# LoraFtdi.net
KiCad netlist of a schematic drawn in Altium Designer
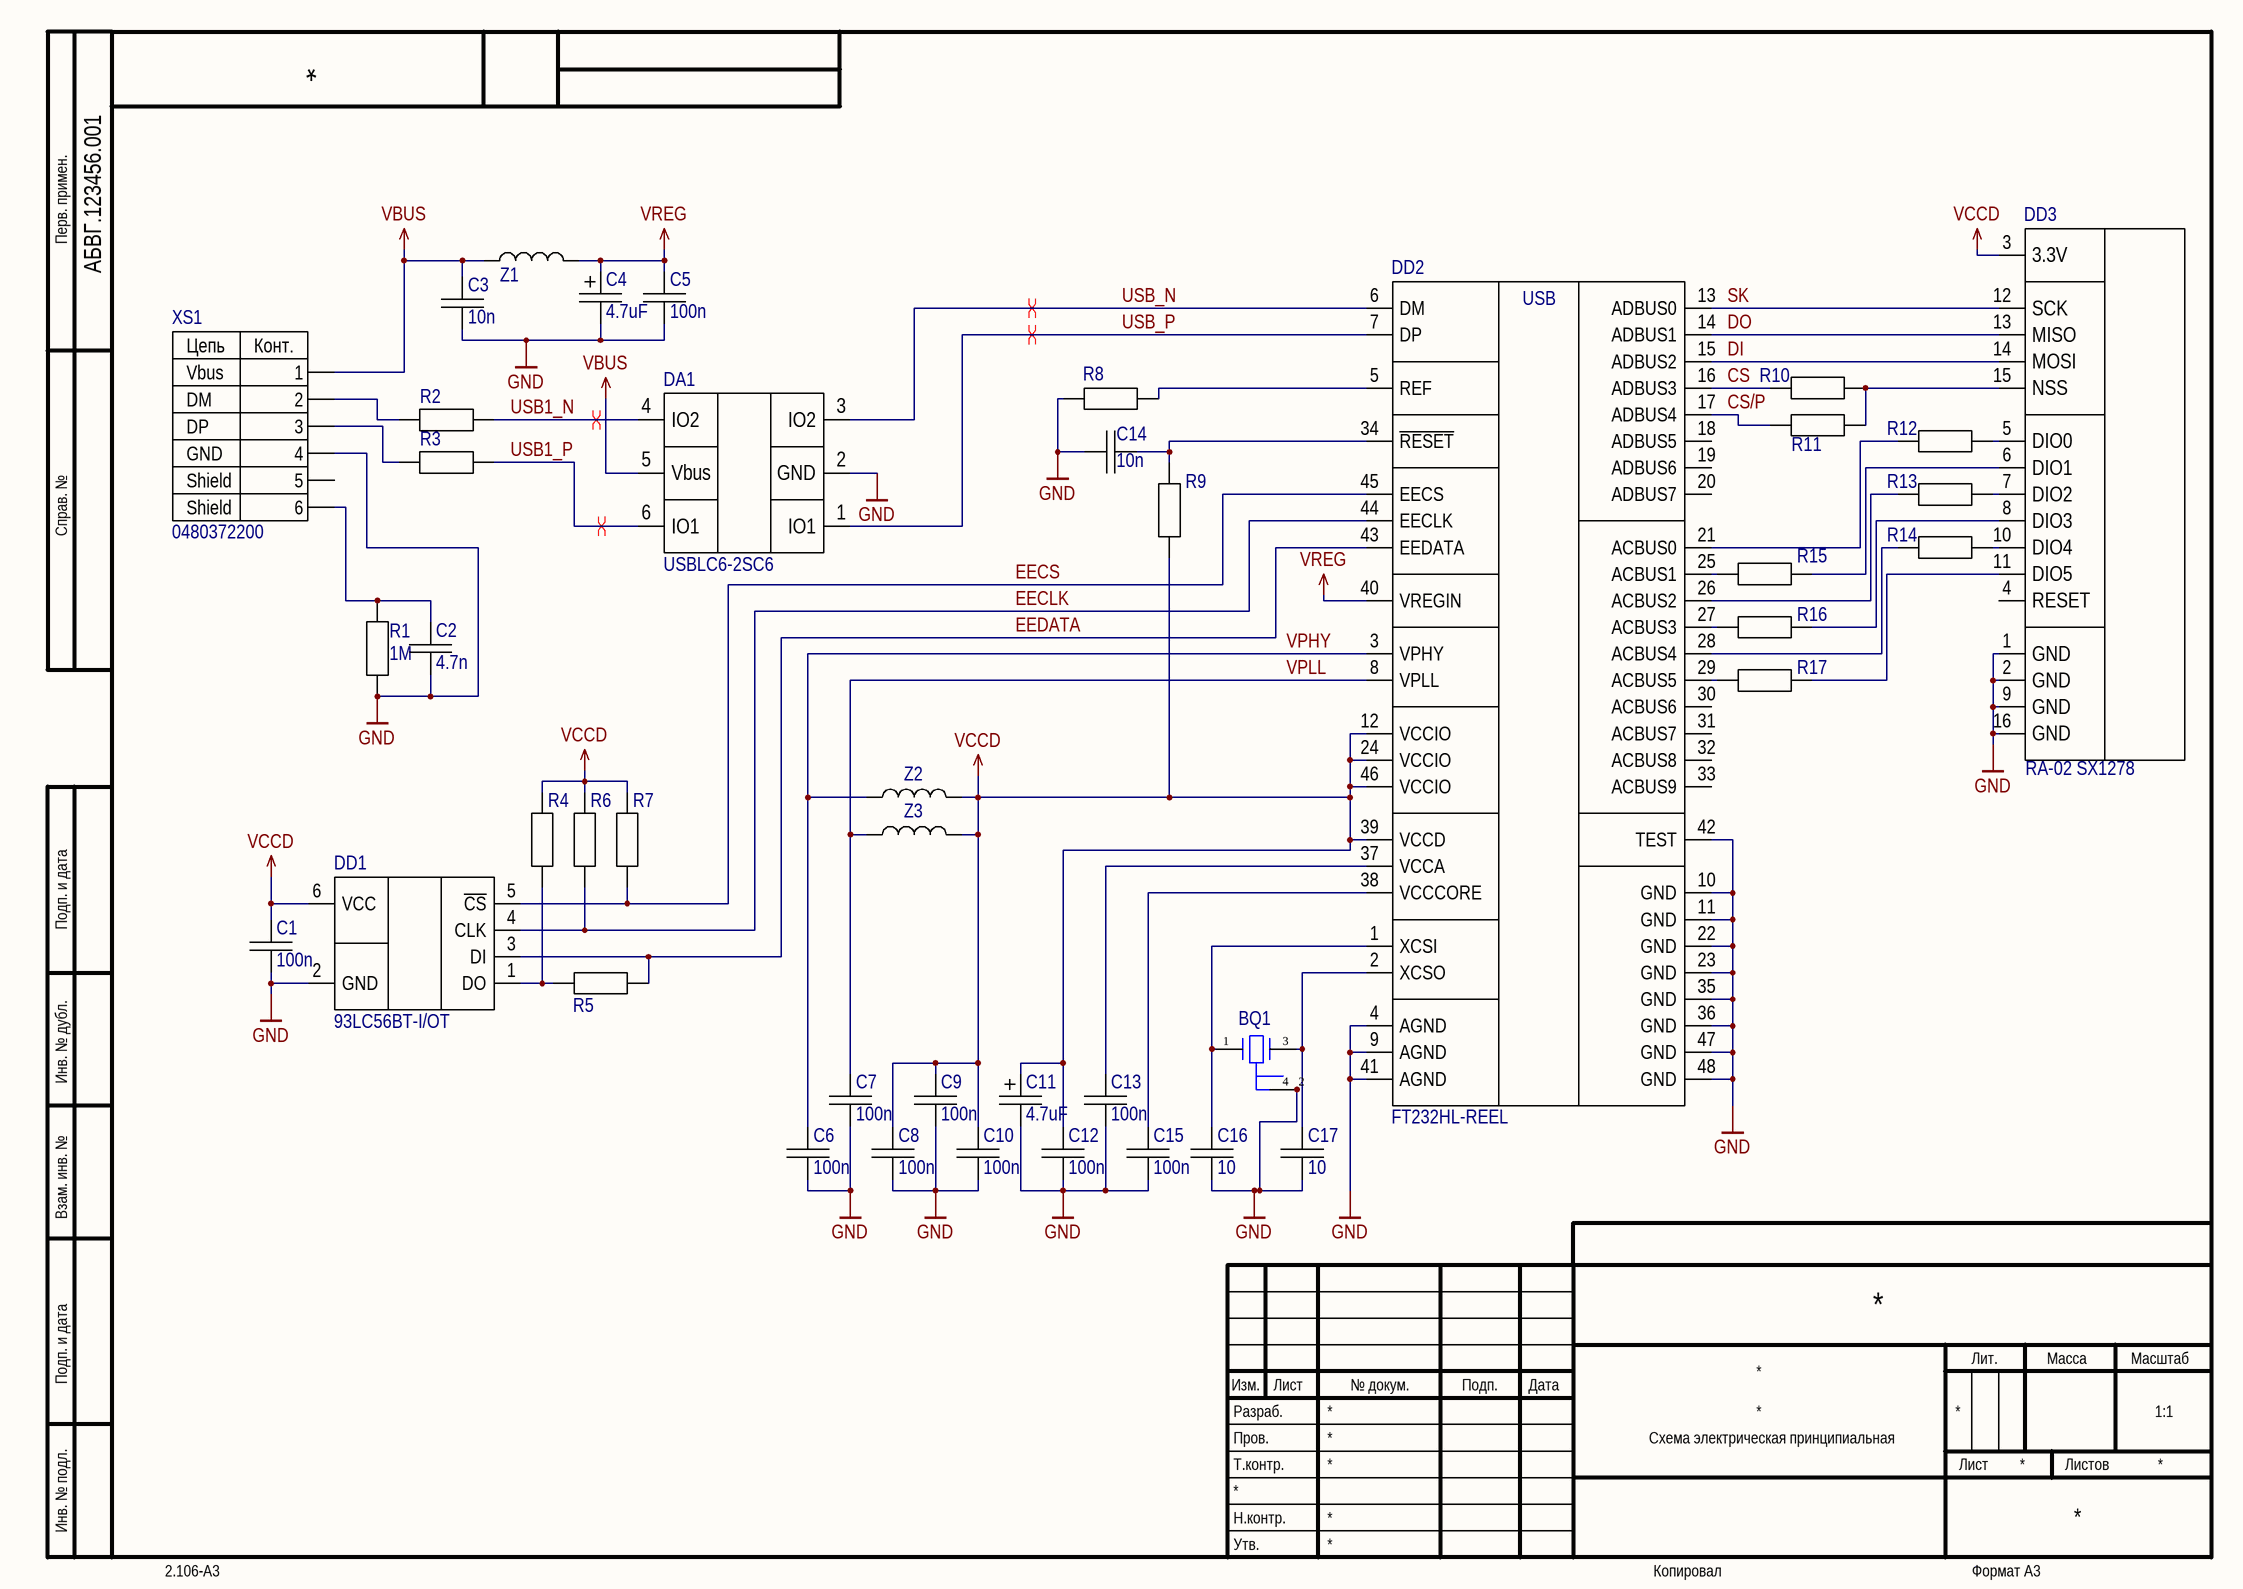
[diagram p0: LoraFtdi.SchDoc]

(export (version "E")
  (design (tool "Eeschema 10.0.6"))
  (components
    (comp (ref "BQ1")
      (value "ABM8G-12.000MHZ-4Y-T3")
      (footprint "Abracon_ABM8G_0")
      (libsource (lib "Crys_Abracon_ABM8G-12.000MHZ-4Y-T3_eec") (part "ABM8G-12.000MHZ-4Y-T3"))
    )
    (comp (ref "C1")
      (value "100n")
      (footprint "1608[0603]")
      (description "Конденсатор 1.6x0.8 мм")
      (fields (field (name "TOLERANCE") "±10%"))
      (libsource (lib "RPSLib") (part "CC1608"))
    )
    (comp (ref "C2")
      (value "4.7n")
      (footprint "1608[0603]")
      (description "Конденсатор 1.6x0.8 мм")
      (fields (field (name "TOLERANCE") "±10%"))
      (libsource (lib "RPSLib") (part "CC1608"))
    )
    (comp (ref "C3")
      (value "10n")
      (footprint "CAPC1608X09L")
      (description "Конденсатор 1.6x0.8 мм")
      (fields (field (name "TOLERANCE") "±10%"))
      (libsource (lib "RPSLib") (part "CC1608"))
    )
    (comp (ref "C4")
      (value "4.7uF")
      (footprint "CAPMP3216X16N-A")
      (description "Tantalum Surface Mount Capacitor, Size A")
      (fields (field (name "VOLTAGE") "16"))
      (libsource (lib "RPSLib") (part "CT3216-A"))
    )
    (comp (ref "C5")
      (value "100n")
      (footprint "CAPC1608X09L")
      (description "Конденсатор 1.6x0.8 мм")
      (fields (field (name "TOLERANCE") "±10%"))
      (libsource (lib "RPSLib") (part "CC1608"))
    )
    (comp (ref "C6")
      (value "100n")
      (footprint "CAPC1608X09L")
      (description "Конденсатор 1.6x0.8 мм")
      (fields (field (name "TOLERANCE") "±10%"))
      (libsource (lib "RPSLib") (part "CC1608"))
    )
    (comp (ref "C7")
      (value "100n")
      (footprint "CAPC1608X09L")
      (description "Конденсатор 1.6x0.8 мм")
      (fields (field (name "TOLERANCE") "±10%"))
      (libsource (lib "RPSLib") (part "CC1608"))
    )
    (comp (ref "C8")
      (value "100n")
      (footprint "CAPC1608X09L")
      (description "Конденсатор 1.6x0.8 мм")
      (fields (field (name "TOLERANCE") "±10%"))
      (libsource (lib "RPSLib") (part "CC1608"))
    )
    (comp (ref "C9")
      (value "100n")
      (footprint "CAPC1608X09L")
      (description "Конденсатор 1.6x0.8 мм")
      (fields (field (name "TOLERANCE") "±10%"))
      (libsource (lib "RPSLib") (part "CC1608"))
    )
    (comp (ref "C10")
      (value "100n")
      (footprint "CAPC1608X09L")
      (description "Конденсатор 1.6x0.8 мм")
      (fields (field (name "TOLERANCE") "±10%"))
      (libsource (lib "RPSLib") (part "CC1608"))
    )
    (comp (ref "C11")
      (value "4.7uF")
      (footprint "CAPMP3216X16N-A")
      (description "Tantalum Surface Mount Capacitor, Size A")
      (fields (field (name "VOLTAGE") "16"))
      (libsource (lib "RPSLib") (part "CT3216-A"))
    )
    (comp (ref "C12")
      (value "100n")
      (footprint "CAPC1608X09L")
      (description "Конденсатор 1.6x0.8 мм")
      (fields (field (name "TOLERANCE") "±10%"))
      (libsource (lib "RPSLib") (part "CC1608"))
    )
    (comp (ref "C13")
      (value "100n")
      (footprint "CAPC1608X09L")
      (description "Конденсатор 1.6x0.8 мм")
      (fields (field (name "TOLERANCE") "±10%"))
      (libsource (lib "RPSLib") (part "CC1608"))
    )
    (comp (ref "C14")
      (value "10n")
      (footprint "CAPC1608X09L")
      (description "Конденсатор 1.6x0.8 мм")
      (fields (field (name "TOLERANCE") "±10%"))
      (libsource (lib "RPSLib") (part "CC1608"))
    )
    (comp (ref "C15")
      (value "100n")
      (footprint "CAPC1608X09L")
      (description "Конденсатор 1.6x0.8 мм")
      (fields (field (name "TOLERANCE") "±10%"))
      (libsource (lib "RPSLib") (part "CC1608"))
    )
    (comp (ref "C16")
      (value "10")
      (footprint "CAPC1608X09L")
      (description "Конденсатор 1.6x0.8 мм")
      (fields (field (name "TOLERANCE") "±10%"))
      (libsource (lib "RPSLib") (part "CC1608"))
    )
    (comp (ref "C17")
      (value "10")
      (footprint "1608[0603]")
      (description "Конденсатор 1.6x0.8 мм")
      (fields (field (name "TOLERANCE") "±10%"))
      (libsource (lib "RPSLib") (part "CC1608"))
    )
    (comp (ref "DA1")
      (value "USBLC6-2SC6")
      (footprint "SOT95P280X145-6N")
      (description "USB protection IC")
      (fields (field (name "MANUFACTURER") "STMicroelectronics"))
      (libsource (lib "RPSLib") (part "USBLC6-2SC6"))
    )
    (comp (ref "DD1")
      (value "93LC56BT-I/OT")
      (footprint "SOT95P280X145-6N")
      (description "IC EEPROM 2K SPI 2MHZ SOT23-6")
      (fields (field (name "MANUFACTURER") "Microchip"))
      (libsource (lib "RPSLib") (part "93LC56BT-I/OT"))
    )
    (comp (ref "DD2")
      (value "FT232HL-REEL")
      (footprint "TSQFP50P900X900X160-48N")
      (description "IC HS USB TO UART/FIFO 48LQFP")
      (fields (field (name "MANUFACTURER") "FTDI"))
      (libsource (lib "RPSLib") (part "FT232HL-REEL"))
    )
    (comp (ref "DD3") (value "RA-02 SX1278") (footprint "RA-02") (libsource (lib "RA-02") (part "RA-02")))
    (comp (ref "R1")
      (value "1M")
      (footprint "J1-0603")
      (description "Резистор 1.6x0.8 мм")
      (fields (field (name "TOLERANCE") "±5%") (field (name "MANUFACTURER PART NUMBER") "RC0603JR-071ML"))
      (libsource (lib "RPSLib") (part "R1608"))
    )
    (comp (ref "R2")
      (value "R1608")
      (footprint "RESC1608X05N")
      (description "Резистор 1.6x0.8 мм")
      (fields (field (name "TOLERANCE") "±1%"))
      (libsource (lib "RPSLib") (part "R1608"))
    )
    (comp (ref "R3")
      (value "R1608")
      (footprint "RESC1608X05N")
      (description "Резистор 1.6x0.8 мм")
      (fields (field (name "TOLERANCE") "±1%"))
      (libsource (lib "RPSLib") (part "R1608"))
    )
    (comp (ref "R4")
      (value "R1608")
      (footprint "RESC1608X05N")
      (description "Резистор 1.6x0.8 мм")
      (fields (field (name "TOLERANCE") "±5%"))
      (libsource (lib "RPSLib") (part "R1608"))
    )
    (comp (ref "R5")
      (value "R1608")
      (footprint "RESC1608X05N")
      (description "Резистор 1.6x0.8 мм")
      (fields (field (name "TOLERANCE") "±5%"))
      (libsource (lib "RPSLib") (part "R1608"))
    )
    (comp (ref "R6")
      (value "R1608")
      (footprint "RESC1608X05N")
      (description "Резистор 1.6x0.8 мм")
      (fields (field (name "TOLERANCE") "±5%"))
      (libsource (lib "RPSLib") (part "R1608"))
    )
    (comp (ref "R7")
      (value "R1608")
      (footprint "RESC1608X05N")
      (description "Резистор 1.6x0.8 мм")
      (fields (field (name "TOLERANCE") "±5%"))
      (libsource (lib "RPSLib") (part "R1608"))
    )
    (comp (ref "R8")
      (value "R1608")
      (footprint "RESC1608X05N")
      (description "Резистор 1.6x0.8 мм")
      (fields (field (name "TOLERANCE") "±5%"))
      (libsource (lib "RPSLib") (part "R1608"))
    )
    (comp (ref "R9")
      (value "R1608")
      (footprint "RESC1608X05N")
      (description "Резистор 1.6x0.8 мм")
      (fields (field (name "TOLERANCE") "±5%"))
      (libsource (lib "RPSLib") (part "R1608"))
    )
    (comp (ref "R10")
      (value "R0603")
      (footprint "RESC0603X02N")
      (description "Резистор 0.6x0.3 мм")
      (libsource (lib "RPSLib") (part "R0603"))
    )
    (comp (ref "R11")
      (value "R0603")
      (footprint "RESC0603X02N")
      (description "Резистор 0.6x0.3 мм")
      (libsource (lib "RPSLib") (part "R0603"))
    )
    (comp (ref "R12")
      (value "R0603")
      (footprint "RESC0603X02N")
      (description "Резистор 0.6x0.3 мм")
      (libsource (lib "RPSLib") (part "R0603"))
    )
    (comp (ref "R13")
      (value "R0603")
      (footprint "RESC0603X02N")
      (description "Резистор 0.6x0.3 мм")
      (libsource (lib "RPSLib") (part "R0603"))
    )
    (comp (ref "R14")
      (value "R0603")
      (footprint "RESC0603X02N")
      (description "Резистор 0.6x0.3 мм")
      (libsource (lib "RPSLib") (part "R0603"))
    )
    (comp (ref "R15")
      (value "R0603")
      (footprint "RESC0603X02N")
      (description "Резистор 0.6x0.3 мм")
      (libsource (lib "RPSLib") (part "R0603"))
    )
    (comp (ref "R16")
      (value "R0603")
      (footprint "RESC0603X02N")
      (description "Резистор 0.6x0.3 мм")
      (libsource (lib "RPSLib") (part "R0603"))
    )
    (comp (ref "R17")
      (value "R0603")
      (footprint "RESC0603X02N")
      (description "Резистор 0.6x0.3 мм")
      (libsource (lib "RPSLib") (part "R0603"))
    )
    (comp (ref "XS1")
      (value "Conn_Molex_0480372200_eec")
      (footprint "Molex_0480372200_0")
      (description "CONN PLUG USB A 4POS SMD R/A")
      (fields
        (field (name "MANUFACTURER") "Molex")
        (field (name "MOUSER PART NUMBER") "538-48037-2200")
        (field (name "PART NUMBER") "0480372200")
      )
      (libsource (lib "Conn_Molex_0480372200_eec") (part "Conn_Molex_0480372200_eec"))
    )
    (comp (ref "Z1")
      (value "BLM18AG601SN1D")
      (footprint "INDC1608X08N_BLM18AG")
      (description "FERRITE CHIP 600 OHM 500MA 0603")
      (fields (field (name "MANUFACTURER") "Murata") (field (name "TOLERANCE") "25%"))
      (libsource (lib "RPSLib") (part "BLM18AG601SN1D"))
    )
    (comp (ref "Z2")
      (value "BLM18AG601SN1D")
      (footprint "INDC1608L")
      (description "FERRITE CHIP 600 OHM 500MA 0603")
      (fields (field (name "MANUFACTURER") "Murata") (field (name "TOLERANCE") "25%"))
      (libsource (lib "RPSLib") (part "BLM18AG601SN1D"))
    )
    (comp (ref "Z3")
      (value "BLM18AG601SN1D")
      (footprint "INDC1608L")
      (description "FERRITE CHIP 600 OHM 500MA 0603")
      (fields (field (name "MANUFACTURER") "Murata") (field (name "TOLERANCE") "25%"))
      (libsource (lib "RPSLib") (part "BLM18AG601SN1D"))
    )
  )
  (nets
    (net (code "1") (name "/CS") (class "Default")
      (node (ref "DD2") (pin "16") (pinfunction "ADBUS3_16") (pintype "passive"))
      (node (ref "R10") (pin "1") (pinfunction "1_1") (pintype "passive"))
    )
    (net (code "2") (name "/CS{slash}P") (class "Default")
      (node (ref "DD2") (pin "17") (pinfunction "ADBUS4_17") (pintype "passive"))
      (node (ref "R11") (pin "1") (pinfunction "1_1") (pintype "passive"))
    )
    (net (code "3") (name "/DI") (class "Default")
      (node (ref "DD2") (pin "15") (pinfunction "ADBUS2_15") (pintype "passive"))
      (node (ref "DD3") (pin "14") (pinfunction "MOSI_14") (pintype "passive"))
    )
    (net (code "4") (name "/DO") (class "Default")
      (node (ref "DD2") (pin "14") (pinfunction "ADBUS1_14") (pintype "passive"))
      (node (ref "DD3") (pin "13") (pinfunction "MISO_13") (pintype "passive"))
    )
    (net (code "5") (name "/EECLK") (class "Default")
      (node (ref "DD1") (pin "4") (pinfunction "CLK_4") (pintype "passive"))
      (node (ref "DD2") (pin "44") (pinfunction "EECLK_44") (pintype "passive"))
      (node (ref "R6") (pin "1") (pinfunction "1_1") (pintype "passive"))
    )
    (net (code "6") (name "/EECS") (class "Default")
      (node (ref "DD1") (pin "5") (pinfunction "~{CS}_5") (pintype "passive"))
      (node (ref "DD2") (pin "45") (pinfunction "EECS_45") (pintype "passive"))
      (node (ref "R7") (pin "1") (pinfunction "1_1") (pintype "passive"))
    )
    (net (code "7") (name "/EEDATA") (class "Default")
      (node (ref "DD1") (pin "3") (pinfunction "DI_3") (pintype "passive"))
      (node (ref "DD2") (pin "43") (pinfunction "EEDATA_43") (pintype "passive"))
      (node (ref "R5") (pin "1") (pinfunction "1_1") (pintype "passive"))
    )
    (net (code "8") (name "/SK") (class "Default")
      (node (ref "DD2") (pin "13") (pinfunction "ADBUS0_13") (pintype "passive"))
      (node (ref "DD3") (pin "12") (pinfunction "SCK_12") (pintype "passive"))
    )
    (net (code "9") (name "/USB1_N") (class "Default")
      (node (ref "DA1") (pin "4") (pinfunction "IO2_4") (pintype "passive"))
      (node (ref "R2") (pin "1") (pinfunction "1_1") (pintype "passive"))
    )
    (net (code "10") (name "/USB1_P") (class "Default")
      (node (ref "DA1") (pin "6") (pinfunction "IO1_6") (pintype "passive"))
      (node (ref "R3") (pin "1") (pinfunction "1_1") (pintype "passive"))
    )
    (net (code "11") (name "/USB_N") (class "Default")
      (node (ref "DA1") (pin "3") (pinfunction "IO2_3") (pintype "passive"))
      (node (ref "DD2") (pin "6") (pinfunction "DM_6") (pintype "passive"))
    )
    (net (code "12") (name "/USB_P") (class "Default")
      (node (ref "DA1") (pin "1") (pinfunction "IO1_1") (pintype "passive"))
      (node (ref "DD2") (pin "7") (pinfunction "DP_7") (pintype "passive"))
    )
    (net (code "13") (name "/VPHY") (class "Default")
      (node (ref "C6") (pin "2") (pinfunction "2_2") (pintype "passive"))
      (node (ref "DD2") (pin "3") (pinfunction "VPHY_3") (pintype "passive"))
      (node (ref "Z2") (pin "1") (pinfunction "1_1") (pintype "passive"))
    )
    (net (code "14") (name "/VPLL") (class "Default")
      (node (ref "C7") (pin "2") (pinfunction "2_2") (pintype "passive"))
      (node (ref "DD2") (pin "8") (pinfunction "VPLL_8") (pintype "passive"))
      (node (ref "Z3") (pin "1") (pinfunction "1_1") (pintype "passive"))
    )
    (net (code "15") (name "GND") (class "Default")
      (node (ref "BQ1") (pin "2") (pinfunction "GND_2") (pintype "passive"))
      (node (ref "BQ1") (pin "4") (pinfunction "GND_4") (pintype "passive"))
      (node (ref "C1") (pin "1") (pinfunction "1_1") (pintype "passive"))
      (node (ref "C10") (pin "1") (pinfunction "1_1") (pintype "passive"))
      (node (ref "C11") (pin "2") (pinfunction "2_2") (pintype "passive"))
      (node (ref "C12") (pin "1") (pinfunction "1_1") (pintype "passive"))
      (node (ref "C13") (pin "1") (pinfunction "1_1") (pintype "passive"))
      (node (ref "C14") (pin "2") (pinfunction "2_2") (pintype "passive"))
      (node (ref "C15") (pin "1") (pinfunction "1_1") (pintype "passive"))
      (node (ref "C16") (pin "1") (pinfunction "1_1") (pintype "passive"))
      (node (ref "C17") (pin "1") (pinfunction "1_1") (pintype "passive"))
      (node (ref "C2") (pin "1") (pinfunction "1_1") (pintype "passive"))
      (node (ref "C3") (pin "1") (pinfunction "1_1") (pintype "passive"))
      (node (ref "C4") (pin "2") (pinfunction "2_2") (pintype "passive"))
      (node (ref "C5") (pin "1") (pinfunction "1_1") (pintype "passive"))
      (node (ref "C6") (pin "1") (pinfunction "1_1") (pintype "passive"))
      (node (ref "C7") (pin "1") (pinfunction "1_1") (pintype "passive"))
      (node (ref "C8") (pin "1") (pinfunction "1_1") (pintype "passive"))
      (node (ref "C9") (pin "1") (pinfunction "1_1") (pintype "passive"))
      (node (ref "DA1") (pin "2") (pinfunction "GND_2") (pintype "passive"))
      (node (ref "DD1") (pin "2") (pinfunction "GND_2") (pintype "passive"))
      (node (ref "DD2") (pin "10") (pinfunction "GND_10") (pintype "passive"))
      (node (ref "DD2") (pin "11") (pinfunction "GND_11") (pintype "passive"))
      (node (ref "DD2") (pin "22") (pinfunction "GND_22") (pintype "passive"))
      (node (ref "DD2") (pin "23") (pinfunction "GND_23") (pintype "passive"))
      (node (ref "DD2") (pin "35") (pinfunction "GND_35") (pintype "passive"))
      (node (ref "DD2") (pin "36") (pinfunction "GND_36") (pintype "passive"))
      (node (ref "DD2") (pin "4") (pinfunction "AGND_4") (pintype "passive"))
      (node (ref "DD2") (pin "41") (pinfunction "AGND_41") (pintype "passive"))
      (node (ref "DD2") (pin "42") (pinfunction "TEST_42") (pintype "passive"))
      (node (ref "DD2") (pin "47") (pinfunction "GND_47") (pintype "passive"))
      (node (ref "DD2") (pin "48") (pinfunction "GND_48") (pintype "passive"))
      (node (ref "DD2") (pin "9") (pinfunction "AGND_9") (pintype "passive"))
      (node (ref "DD3") (pin "1") (pinfunction "GND_1") (pintype "passive"))
      (node (ref "DD3") (pin "16") (pinfunction "GND_16") (pintype "passive"))
      (node (ref "DD3") (pin "2") (pinfunction "GND_2") (pintype "passive"))
      (node (ref "DD3") (pin "9") (pinfunction "GND_9") (pintype "passive"))
      (node (ref "R1") (pin "2") (pinfunction "2_2") (pintype "passive"))
      (node (ref "R8") (pin "2") (pinfunction "2_2") (pintype "passive"))
      (node (ref "XS1") (pin "4") (pinfunction "4_4") (pintype "passive"))
    )
    (net (code "16") (name "Net-(DD1-DO)") (class "Default")
      (node (ref "DD1") (pin "1") (pinfunction "DO_1") (pintype "passive"))
      (node (ref "R4") (pin "1") (pinfunction "1_1") (pintype "passive"))
      (node (ref "R5") (pin "2") (pinfunction "2_2") (pintype "passive"))
    )
    (net (code "17") (name "Net-(DD2-ACBUS0)") (class "Default")
      (node (ref "DD2") (pin "21") (pinfunction "ACBUS0_21") (pintype "passive"))
      (node (ref "R12") (pin "1") (pinfunction "1_1") (pintype "passive"))
    )
    (net (code "18") (name "Net-(DD2-ACBUS1)") (class "Default")
      (node (ref "DD2") (pin "25") (pinfunction "ACBUS1_25") (pintype "passive"))
      (node (ref "R15") (pin "1") (pinfunction "1_1") (pintype "passive"))
    )
    (net (code "19") (name "Net-(DD2-ACBUS2)") (class "Default")
      (node (ref "DD2") (pin "26") (pinfunction "ACBUS2_26") (pintype "passive"))
      (node (ref "R13") (pin "1") (pinfunction "1_1") (pintype "passive"))
    )
    (net (code "20") (name "Net-(DD2-ACBUS3)") (class "Default")
      (node (ref "DD2") (pin "27") (pinfunction "ACBUS3_27") (pintype "passive"))
      (node (ref "R16") (pin "1") (pinfunction "1_1") (pintype "passive"))
    )
    (net (code "21") (name "Net-(DD2-ACBUS4)") (class "Default")
      (node (ref "DD2") (pin "28") (pinfunction "ACBUS4_28") (pintype "passive"))
      (node (ref "R14") (pin "1") (pinfunction "1_1") (pintype "passive"))
    )
    (net (code "22") (name "Net-(DD2-ACBUS5)") (class "Default")
      (node (ref "DD2") (pin "29") (pinfunction "ACBUS5_29") (pintype "passive"))
      (node (ref "R17") (pin "1") (pinfunction "1_1") (pintype "passive"))
    )
    (net (code "23") (name "Net-(DD2-REF)") (class "Default")
      (node (ref "DD2") (pin "5") (pinfunction "REF_5") (pintype "passive"))
      (node (ref "R8") (pin "1") (pinfunction "1_1") (pintype "passive"))
    )
    (net (code "24") (name "Net-(DD2-VCCA)") (class "Default")
      (node (ref "C13") (pin "2") (pinfunction "2_2") (pintype "passive"))
      (node (ref "DD2") (pin "37") (pinfunction "VCCA_37") (pintype "passive"))
    )
    (net (code "25") (name "Net-(DD2-VCCCORE)") (class "Default")
      (node (ref "C15") (pin "2") (pinfunction "2_2") (pintype "passive"))
      (node (ref "DD2") (pin "38") (pinfunction "VCCCORE_38") (pintype "passive"))
    )
    (net (code "26") (name "Net-(DD2-XCSI)") (class "Default")
      (node (ref "BQ1") (pin "1") (pinfunction "1_1") (pintype "passive"))
      (node (ref "C16") (pin "2") (pinfunction "2_2") (pintype "passive"))
      (node (ref "DD2") (pin "1") (pinfunction "XCSI_1") (pintype "passive"))
    )
    (net (code "27") (name "Net-(DD2-XCSO)") (class "Default")
      (node (ref "BQ1") (pin "3") (pinfunction "3_3") (pintype "passive"))
      (node (ref "C17") (pin "2") (pinfunction "2_2") (pintype "passive"))
      (node (ref "DD2") (pin "2") (pinfunction "XCSO_2") (pintype "passive"))
    )
    (net (code "28") (name "Net-(DD2-~{RESET})") (class "Default")
      (node (ref "C14") (pin "1") (pinfunction "1_1") (pintype "passive"))
      (node (ref "DD2") (pin "34") (pinfunction "~{RESET}_34") (pintype "passive"))
      (node (ref "R9") (pin "2") (pinfunction "2_2") (pintype "passive"))
    )
    (net (code "29") (name "Net-(DD3-DIO0)") (class "Default")
      (node (ref "DD3") (pin "5") (pinfunction "DIO0_5") (pintype "passive"))
      (node (ref "R12") (pin "2") (pinfunction "2_2") (pintype "passive"))
    )
    (net (code "30") (name "Net-(DD3-DIO1)") (class "Default")
      (node (ref "DD3") (pin "6") (pinfunction "DIO1_6") (pintype "passive"))
      (node (ref "R15") (pin "2") (pinfunction "2_2") (pintype "passive"))
    )
    (net (code "31") (name "Net-(DD3-DIO2)") (class "Default")
      (node (ref "DD3") (pin "7") (pinfunction "DIO2_7") (pintype "passive"))
      (node (ref "R13") (pin "2") (pinfunction "2_2") (pintype "passive"))
    )
    (net (code "32") (name "Net-(DD3-DIO3)") (class "Default")
      (node (ref "DD3") (pin "8") (pinfunction "DIO3_8") (pintype "passive"))
      (node (ref "R16") (pin "2") (pinfunction "2_2") (pintype "passive"))
    )
    (net (code "33") (name "Net-(DD3-DIO4)") (class "Default")
      (node (ref "DD3") (pin "10") (pinfunction "DIO4_10") (pintype "passive"))
      (node (ref "R14") (pin "2") (pinfunction "2_2") (pintype "passive"))
    )
    (net (code "34") (name "Net-(DD3-DIO5)") (class "Default")
      (node (ref "DD3") (pin "11") (pinfunction "DIO5_11") (pintype "passive"))
      (node (ref "R17") (pin "2") (pinfunction "2_2") (pintype "passive"))
    )
    (net (code "35") (name "Net-(DD3-NSS)") (class "Default")
      (node (ref "DD3") (pin "15") (pinfunction "NSS_15") (pintype "passive"))
      (node (ref "R10") (pin "2") (pinfunction "2_2") (pintype "passive"))
      (node (ref "R11") (pin "2") (pinfunction "2_2") (pintype "passive"))
    )
    (net (code "36") (name "Net-(R2-Pad2)") (class "Default")
      (node (ref "R2") (pin "2") (pinfunction "2_2") (pintype "passive"))
      (node (ref "XS1") (pin "2") (pinfunction "2_2") (pintype "passive"))
    )
    (net (code "37") (name "Net-(R3-Pad2)") (class "Default")
      (node (ref "R3") (pin "2") (pinfunction "2_2") (pintype "passive"))
      (node (ref "XS1") (pin "3") (pinfunction "3_3") (pintype "passive"))
    )
    (net (code "38") (name "Net-(XS1-MNT_2)") (class "Default")
      (node (ref "C2") (pin "2") (pinfunction "2_2") (pintype "passive"))
      (node (ref "R1") (pin "1") (pinfunction "1_1") (pintype "passive"))
      (node (ref "XS1") (pin "6") (pinfunction "MNT_2_6") (pintype "passive"))
    )
    (net (code "39") (name "VBUS") (class "Default")
      (node (ref "C3") (pin "2") (pinfunction "2_2") (pintype "passive"))
      (node (ref "DA1") (pin "5") (pinfunction "Vbus_5") (pintype "passive"))
      (node (ref "XS1") (pin "1") (pinfunction "1_1") (pintype "passive"))
      (node (ref "Z1") (pin "1") (pinfunction "1_1") (pintype "passive"))
    )
    (net (code "40") (name "VCCD") (class "Default")
      (node (ref "C1") (pin "2") (pinfunction "2_2") (pintype "passive"))
      (node (ref "C10") (pin "2") (pinfunction "2_2") (pintype "passive"))
      (node (ref "C11") (pin "1") (pinfunction "1_1") (pintype "passive"))
      (node (ref "C12") (pin "2") (pinfunction "2_2") (pintype "passive"))
      (node (ref "C8") (pin "2") (pinfunction "2_2") (pintype "passive"))
      (node (ref "C9") (pin "2") (pinfunction "2_2") (pintype "passive"))
      (node (ref "DD1") (pin "6") (pinfunction "VCC_6") (pintype "passive"))
      (node (ref "DD2") (pin "12") (pinfunction "VCCIO_12") (pintype "passive"))
      (node (ref "DD2") (pin "24") (pinfunction "VCCIO_24") (pintype "passive"))
      (node (ref "DD2") (pin "39") (pinfunction "VCCD_39") (pintype "passive"))
      (node (ref "DD2") (pin "46") (pinfunction "VCCIO_46") (pintype "passive"))
      (node (ref "DD3") (pin "3") (pinfunction "3.3V_3") (pintype "passive"))
      (node (ref "R4") (pin "2") (pinfunction "2_2") (pintype "passive"))
      (node (ref "R6") (pin "2") (pinfunction "2_2") (pintype "passive"))
      (node (ref "R7") (pin "2") (pinfunction "2_2") (pintype "passive"))
      (node (ref "R9") (pin "1") (pinfunction "1_1") (pintype "passive"))
      (node (ref "Z2") (pin "2") (pinfunction "2_2") (pintype "passive"))
      (node (ref "Z3") (pin "2") (pinfunction "2_2") (pintype "passive"))
    )
    (net (code "41") (name "VREG") (class "Default")
      (node (ref "C4") (pin "1") (pinfunction "1_1") (pintype "passive"))
      (node (ref "C5") (pin "2") (pinfunction "2_2") (pintype "passive"))
      (node (ref "DD2") (pin "40") (pinfunction "VREGIN_40") (pintype "passive"))
      (node (ref "Z1") (pin "2") (pinfunction "2_2") (pintype "passive"))
    )
    (net (code "42") (name "unconnected-(DD2-ACBUS6-Pad30)") (class "Default")
      (node (ref "DD2") (pin "30") (pinfunction "ACBUS6_30") (pintype "passive"))
    )
    (net (code "43") (name "unconnected-(DD2-ACBUS7-Pad31)") (class "Default")
      (node (ref "DD2") (pin "31") (pinfunction "ACBUS7_31") (pintype "passive"))
    )
    (net (code "44") (name "unconnected-(DD2-ACBUS8-Pad32)") (class "Default")
      (node (ref "DD2") (pin "32") (pinfunction "ACBUS8_32") (pintype "passive"))
    )
    (net (code "45") (name "unconnected-(DD2-ACBUS9-Pad33)") (class "Default")
      (node (ref "DD2") (pin "33") (pinfunction "ACBUS9_33") (pintype "passive"))
    )
    (net (code "46") (name "unconnected-(DD2-ADBUS5-Pad18)") (class "Default")
      (node (ref "DD2") (pin "18") (pinfunction "ADBUS5_18") (pintype "passive"))
    )
    (net (code "47") (name "unconnected-(DD2-ADBUS6-Pad19)") (class "Default")
      (node (ref "DD2") (pin "19") (pinfunction "ADBUS6_19") (pintype "passive"))
    )
    (net (code "48") (name "unconnected-(DD2-ADBUS7-Pad20)") (class "Default")
      (node (ref "DD2") (pin "20") (pinfunction "ADBUS7_20") (pintype "passive"))
    )
    (net (code "49") (name "unconnected-(DD3-RESET-Pad4)") (class "Default")
      (node (ref "DD3") (pin "4") (pinfunction "RESET_4") (pintype "passive"))
    )
    (net (code "50") (name "unconnected-(XS1-MNT_1-Pad5)") (class "Default")
      (node (ref "XS1") (pin "5") (pinfunction "MNT_1_5") (pintype "passive"))
    )
  )
)
